# Interface_Voltage_Sensor_1.net
KiCad netlist of a schematic drawn in Altium Designer
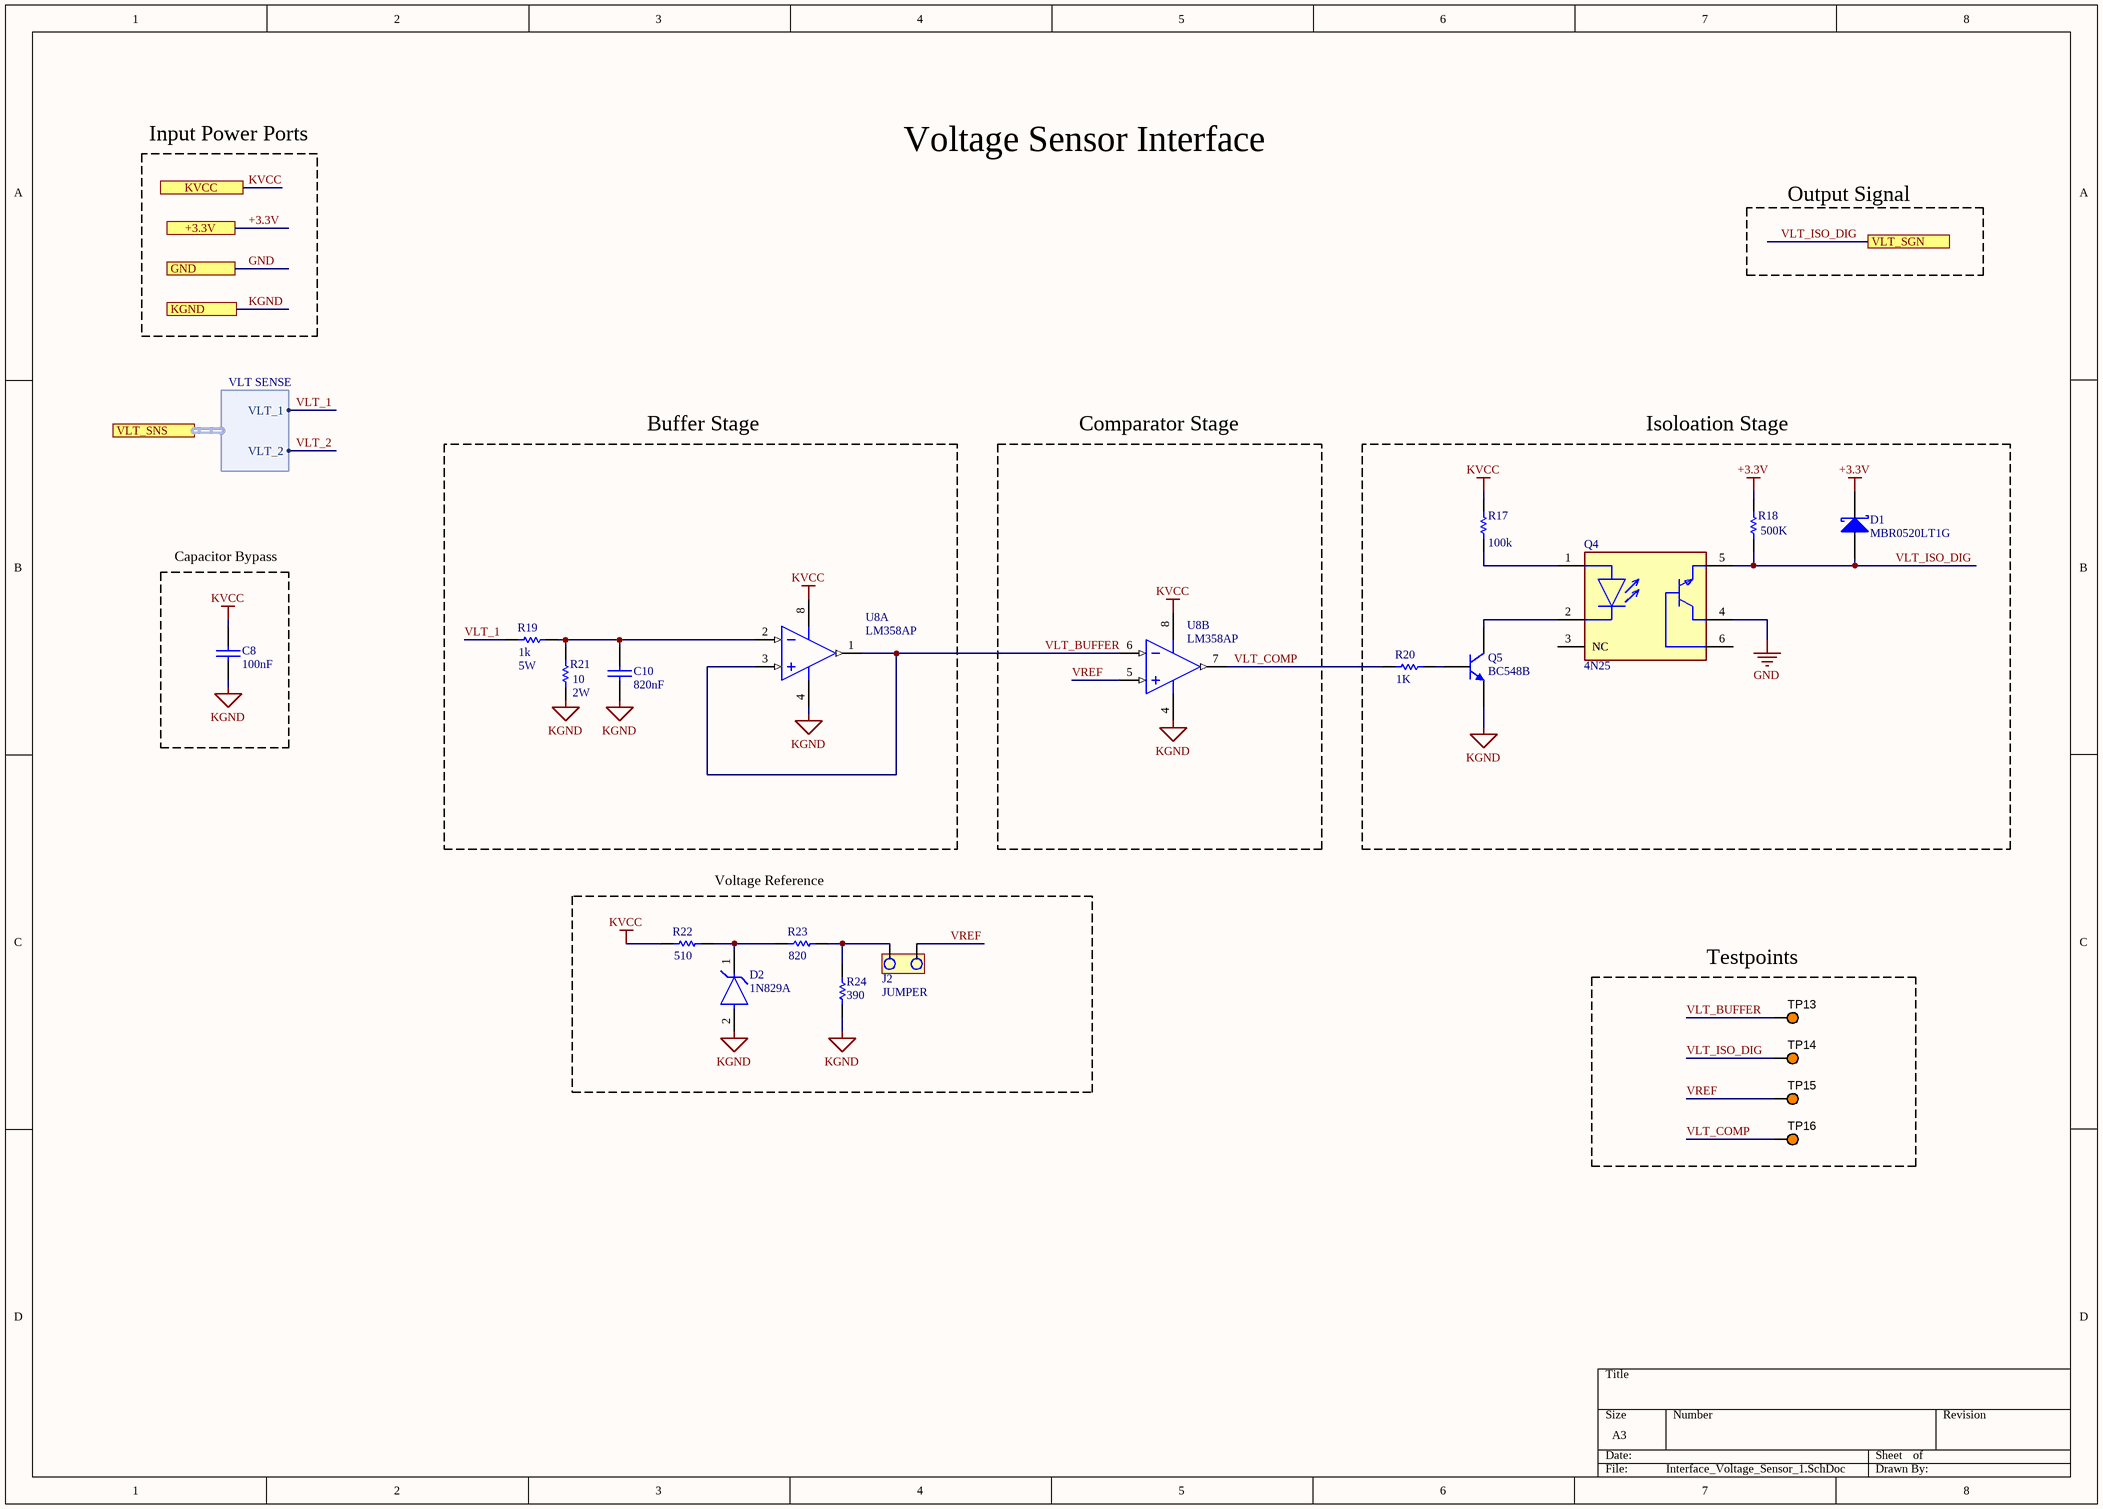
[diagram p0: Interface_Voltage_Sensor_1.SchDoc]

(export (version "E")
  (design (tool "Eeschema 10.0.6"))
  (components
    (comp (ref "C8") (value "100nF") (footprint "CAP200") (libsource (lib "LIBEBAL") (part "CAP")))
    (comp (ref "C10") (value "820nF") (footprint "CAP200") (libsource (lib "LIBEBAL") (part "CAP")))
    (comp (ref "D1")
      (value "MBR0520LT1G")
      (footprint "ONSC-SOD-123-2-425-04_V")
      (description "Schottky Power Rectifier, 20 V, 5.5 A, -65 to 125 degC, 2-Pin SMD, RoHS, Tape and Reel")
      (fields (field (name "MANUFACTURER") "ON Semiconductor"))
      (libsource (lib "TD") (part "DSKY-AK-2"))
    )
    (comp (ref "D2")
      (value "1N829A")
      (footprint "FP-DO-35-MFG")
      (description "Zener Diode, 6.2V V(Z), 4.84%, 0.5W, Silicon, DO-204AA")
      (libsource (lib "TD") (part "f813f71cba58e380607f5dd3caf9714"))
    )
    (comp (ref "J2") (value "JUMPER") (footprint "JUMPER2") (libsource (lib "LIBEBAL") (part "JUMPER")))
    (comp (ref "Q4")
      (value "4N25")
      (footprint "FP-4N25-MFG")
      (description "VISHAY 4N25 Transistor Output Optocoupler, 1 Channel, DIP, 6 Pins, 60 mA, 5 kV, 20 %")
      (libsource (lib "TD") (part "f1df9f29c47de6998195431899ac75d"))
    )
    (comp (ref "Q5")
      (value "BC548B")
      (footprint "TO-226-AA")
      (description "NPN Bipolar Transistor")
      (fields (field (name "PUBLISHER") "Altium Limited"))
      (libsource (lib "Miscellaneous Devices") (part "NPN"))
    )
    (comp (ref "R17")
      (value "100k")
      (footprint "AXIAL-0.3")
      (description "Resistor")
      (fields (field (name "Comment") "Res1") (field (name "PUBLISHER") "Altium Limited"))
      (libsource (lib "Miscellaneous Devices") (part "Res1"))
    )
    (comp (ref "R18")
      (value "500K")
      (footprint "AXIAL-0.3")
      (description "Resistor")
      (fields (field (name "Comment") "Res1") (field (name "PUBLISHER") "Altium Limited"))
      (libsource (lib "Miscellaneous Devices") (part "Res1"))
    )
    (comp (ref "R19")
      (value "5W")
      (footprint "AXIAL-0.3")
      (description "Resistor")
      (fields (field (name "ALTIUM_VALUE") "1k") (field (name "PUBLISHER") "Altium Limited"))
      (libsource (lib "Miscellaneous Devices") (part "Res1"))
    )
    (comp (ref "R20")
      (value "1K")
      (footprint "AXIAL-0.3")
      (description "Resistor")
      (fields (field (name "Comment") "Res1") (field (name "PUBLISHER") "Altium Limited"))
      (libsource (lib "Miscellaneous Devices") (part "Res1"))
    )
    (comp (ref "R21")
      (value "2W")
      (footprint "AXIAL-0.3")
      (description "Resistor")
      (fields (field (name "ALTIUM_VALUE") "10") (field (name "PUBLISHER") "Altium Limited"))
      (libsource (lib "Miscellaneous Devices") (part "Res1"))
    )
    (comp (ref "R22")
      (value "510")
      (footprint "AXIAL-0.3")
      (description "Resistor")
      (fields (field (name "Comment") "Res1") (field (name "PUBLISHER") "Altium Limited"))
      (libsource (lib "Miscellaneous Devices") (part "Res1"))
    )
    (comp (ref "R23")
      (value "820")
      (footprint "AXIAL-0.3")
      (description "Resistor")
      (fields (field (name "Comment") "Res1") (field (name "PUBLISHER") "Altium Limited"))
      (libsource (lib "Miscellaneous Devices") (part "Res1"))
    )
    (comp (ref "R24")
      (value "390")
      (footprint "AXIAL-0.3")
      (description "Resistor")
      (fields (field (name "Comment") "Res1") (field (name "PUBLISHER") "Altium Limited"))
      (libsource (lib "Miscellaneous Devices") (part "Res1"))
    )
    (comp (ref "TP13")
      (value "5003")
      (footprint "KSTN-5003")
      (description "Test Point, Orange, Height 4.6 mm, Tail Length 3 mm, 1-Pin THD, RoHS")
      (fields (field (name "MANUFACTURER") "Keystone"))
      (libsource (lib "TD") (part "TESTPOINT_ORANGE"))
    )
    (comp (ref "TP14")
      (value "5003")
      (footprint "KSTN-5003")
      (description "Test Point, Orange, Height 4.6 mm, Tail Length 3 mm, 1-Pin THD, RoHS")
      (fields (field (name "MANUFACTURER") "Keystone"))
      (libsource (lib "TD") (part "TESTPOINT_ORANGE"))
    )
    (comp (ref "TP15")
      (value "5003")
      (footprint "KSTN-5003")
      (description "Test Point, Orange, Height 4.6 mm, Tail Length 3 mm, 1-Pin THD, RoHS")
      (fields (field (name "MANUFACTURER") "Keystone"))
      (libsource (lib "TD") (part "TESTPOINT_ORANGE"))
    )
    (comp (ref "TP16")
      (value "5003")
      (footprint "KSTN-5003")
      (description "Test Point, Orange, Height 4.6 mm, Tail Length 3 mm, 1-Pin THD, RoHS")
      (fields (field (name "MANUFACTURER") "Keystone"))
      (libsource (lib "TD") (part "TESTPOINT_ORANGE"))
    )
    (comp (ref "U8")
      (value "LM358AP")
      (footprint "P0008A")
      (description "Dual Operational Amplifier, 3 to 32 V, 0 to 70 degC, 8-Pin PDIP (P), Pb-Free (RoHS), Tube")
      (fields (field (name "MANUFACTURER") "Texas Instruments (TI)"))
      (libsource (lib "TD") (part "TI-LM358-8"))
    )
  )
  (nets
    (net (code "3") (name "+3.3V") (class "Default")
      (node (ref "D1") (pin "2") (pinfunction "K_2") (pintype "passive"))
      (node (ref "R18") (pin "2") (pinfunction "2_2") (pintype "passive"))
    )
    (net (code "5") (name "/VLT_1") (class "Default")
      (node (ref "R19") (pin "1") (pinfunction "1_1") (pintype "passive"))
    )
    (net (code "7") (name "/VLT_BUFFER") (class "Default")
      (node (ref "TP13") (pin "1") (pinfunction "1_1") (pintype "passive"))
      (node (ref "U8") (pin "1") (pinfunction "1OUT_1") (pintype "output"))
      (node (ref "U8") (pin "3") (pinfunction "1IN+_3") (pintype "input"))
      (node (ref "U8") (pin "6") (pinfunction "2IN-_6") (pintype "input"))
    )
    (net (code "8") (name "/VLT_COMP") (class "Default")
      (node (ref "R20") (pin "1") (pinfunction "1_1") (pintype "passive"))
      (node (ref "TP16") (pin "1") (pinfunction "1_1") (pintype "passive"))
      (node (ref "U8") (pin "7") (pinfunction "2OUT_7") (pintype "output"))
    )
    (net (code "9") (name "/VLT_ISO_DIG") (class "Default")
      (node (ref "D1") (pin "1") (pinfunction "A_1") (pintype "passive"))
      (node (ref "Q4") (pin "5") (pinfunction "C_5") (pintype "passive"))
      (node (ref "R18") (pin "1") (pinfunction "1_1") (pintype "passive"))
      (node (ref "TP14") (pin "1") (pinfunction "1_1") (pintype "passive"))
    )
    (net (code "10") (name "/VREF") (class "Default")
      (node (ref "J2") (pin "2") (pinfunction "2_2") (pintype "passive"))
      (node (ref "TP15") (pin "1") (pinfunction "1_1") (pintype "passive"))
      (node (ref "U8") (pin "5") (pinfunction "2IN+_5") (pintype "input"))
    )
    (net (code "12") (name "GND") (class "Default")
      (node (ref "Q4") (pin "4") (pinfunction "E_4") (pintype "passive"))
    )
    (net (code "13") (name "KGND") (class "Default")
      (node (ref "C10") (pin "2") (pinfunction "2_2") (pintype "passive"))
      (node (ref "C8") (pin "2") (pinfunction "2_2") (pintype "passive"))
      (node (ref "D2") (pin "2") (pinfunction "A_2") (pintype "passive"))
      (node (ref "Q5") (pin "3") (pinfunction "E_3") (pintype "passive"))
      (node (ref "R21") (pin "1") (pinfunction "1_1") (pintype "passive"))
      (node (ref "R24") (pin "1") (pinfunction "1_1") (pintype "passive"))
      (node (ref "U8") (pin "4") (pinfunction "GND_4") (pintype "power_in"))
    )
    (net (code "14") (name "KVCC") (class "Default")
      (node (ref "C8") (pin "1") (pinfunction "1_1") (pintype "passive"))
      (node (ref "R17") (pin "2") (pinfunction "2_2") (pintype "passive"))
      (node (ref "R22") (pin "1") (pinfunction "1_1") (pintype "passive"))
      (node (ref "U8") (pin "8") (pinfunction "VCC_8") (pintype "power_in"))
    )
    (net (code "15") (name "Net-(D2-C)") (class "Default")
      (node (ref "D2") (pin "1") (pinfunction "C_1") (pintype "passive"))
      (node (ref "R22") (pin "2") (pinfunction "2_2") (pintype "passive"))
      (node (ref "R23") (pin "1") (pinfunction "1_1") (pintype "passive"))
    )
    (net (code "16") (name "Net-(J2-Pad1)") (class "Default")
      (node (ref "J2") (pin "1") (pinfunction "1_1") (pintype "passive"))
      (node (ref "R23") (pin "2") (pinfunction "2_2") (pintype "passive"))
      (node (ref "R24") (pin "2") (pinfunction "2_2") (pintype "passive"))
    )
    (net (code "17") (name "Net-(Q4-A)") (class "Default")
      (node (ref "Q4") (pin "1") (pinfunction "A_1") (pintype "passive"))
      (node (ref "R17") (pin "1") (pinfunction "1_1") (pintype "passive"))
    )
    (net (code "18") (name "Net-(Q5-B)") (class "Default")
      (node (ref "Q5") (pin "2") (pinfunction "B_2") (pintype "passive"))
      (node (ref "R20") (pin "2") (pinfunction "2_2") (pintype "passive"))
    )
    (net (code "19") (name "Net-(Q5-C)") (class "Default")
      (node (ref "Q4") (pin "2") (pinfunction "C_2") (pintype "passive"))
      (node (ref "Q5") (pin "1") (pinfunction "C_1") (pintype "passive"))
    )
    (net (code "20") (name "Net-(U8A-1IN-)") (class "Default")
      (node (ref "C10") (pin "1") (pinfunction "1_1") (pintype "passive"))
      (node (ref "R19") (pin "2") (pinfunction "2_2") (pintype "passive"))
      (node (ref "R21") (pin "2") (pinfunction "2_2") (pintype "passive"))
      (node (ref "U8") (pin "2") (pinfunction "1IN-_2") (pintype "input"))
    )
    (net (code "21") (name "unconnected-(Q4-B-Pad6)") (class "Default")
      (node (ref "Q4") (pin "6") (pinfunction "B_6") (pintype "passive"))
    )
    (net (code "22") (name "unconnected-(Q4-NC-Pad3)") (class "Default")
      (node (ref "Q4") (pin "3") (pinfunction "NC_3") (pintype "passive"))
    )
  )
)
